# Narrow_AAA_sensor.net
KiCad netlist of a schematic drawn in EAGLE
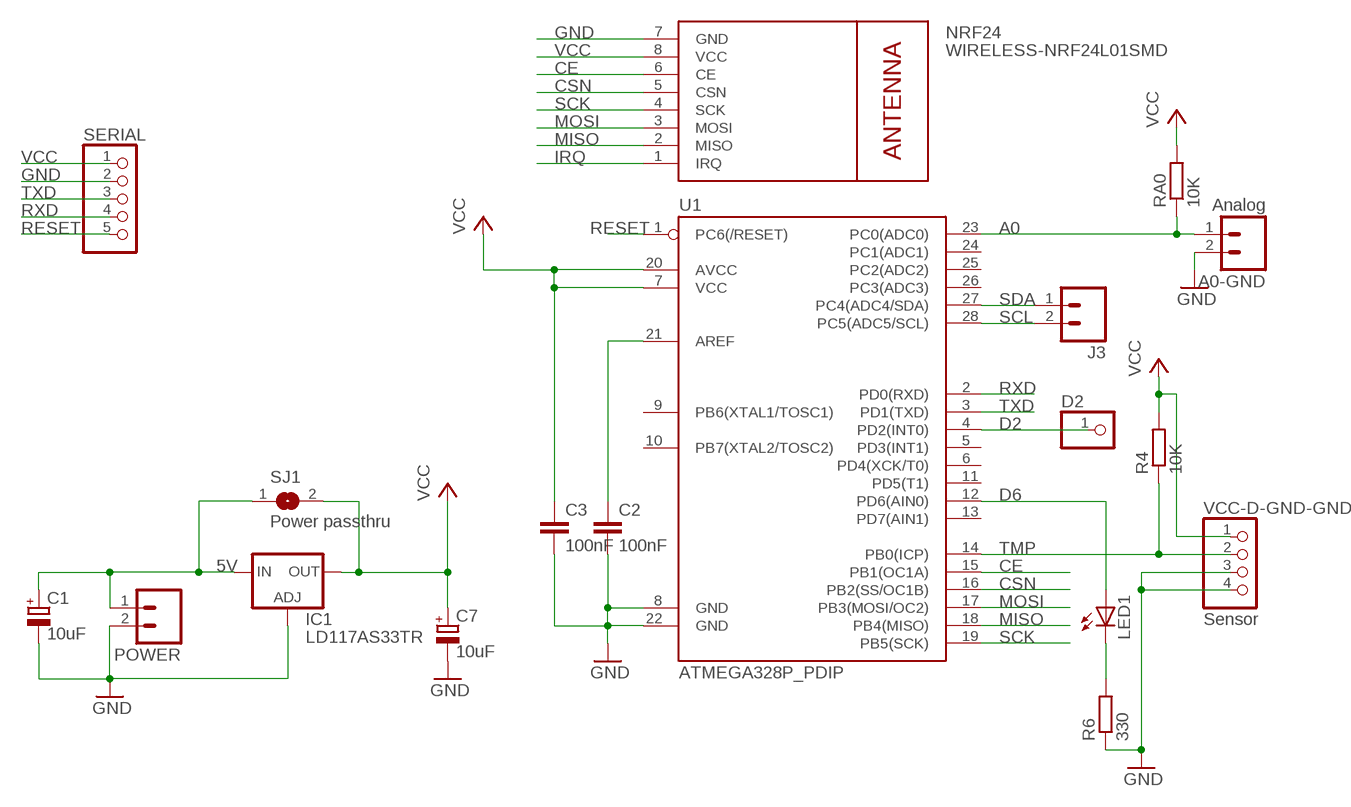
[diagram p0: schematic, sheet 1]

(export (version "E")
  (design (tool "Eeschema 10.0.6"))
  (components
    (comp (ref "A0-GND")
      (value "Analog")
      (footprint "eagle-import:1X02")
      (libsource (lib "eagle-import") (part "M02PTH"))
    )
    (comp (ref "C1")
      (value "10uF")
      (footprint "eagle-import:E2,5-5")
      (libsource (lib "eagle-import") (part "CPOL-EUE2.5-5"))
    )
    (comp (ref "C2")
      (value "100nF")
      (footprint "eagle-import:C025-025X050")
      (libsource (lib "eagle-import") (part "C-EU025-025X050"))
    )
    (comp (ref "C3")
      (value "100nF")
      (footprint "eagle-import:C025-025X050")
      (libsource (lib "eagle-import") (part "C-EU025-025X050"))
    )
    (comp (ref "C7")
      (value "10uF")
      (footprint "eagle-import:E2,5-5")
      (libsource (lib "eagle-import") (part "CPOL-EUE2.5-5"))
    )
    (comp (ref "D2")
      (value "PINHD-1X1")
      (footprint "eagle-import:1X01")
      (libsource (lib "eagle-import") (part "PINHD-1X1"))
    )
    (comp (ref "IC1")
      (value "LD117AS33TR")
      (footprint "eagle-import:SOT223")
      (libsource (lib "eagle-import") (part "LD117A?S33TR"))
    )
    (comp (ref "J3")
      (value "M021X02_NO_SILK")
      (footprint "eagle-import:1X02_NO_SILK")
      (libsource (lib "eagle-import") (part "M021X02_NO_SILK"))
    )
    (comp (ref "LED1")
      (value "LED3MM")
      (footprint "eagle-import:LED3MM")
      (libsource (lib "eagle-import") (part "LED3MM"))
    )
    (comp (ref "NRF24")
      (value "WIRELESS-NRF24L01SMD")
      (footprint "eagle-import:WIRELESS-NRF24L01-SMD")
      (libsource (lib "eagle-import") (part "WIRELESS-NRF24L01SMD"))
    )
    (comp (ref "POWER")
      (value "M021X02_NO_SILK")
      (footprint "eagle-import:1X02_NO_SILK")
      (libsource (lib "eagle-import") (part "M021X02_NO_SILK"))
    )
    (comp (ref "R4")
      (value "10K")
      (footprint "eagle-import:0204_7")
      (libsource (lib "eagle-import") (part "R-EU_0204/7"))
    )
    (comp (ref "R6")
      (value "330")
      (footprint "eagle-import:0204_7")
      (libsource (lib "eagle-import") (part "R-EU_0204/7"))
    )
    (comp (ref "RA0")
      (value "10K")
      (footprint "eagle-import:0204_7")
      (libsource (lib "eagle-import") (part "R-EU_0204/7"))
    )
    (comp (ref "SERIAL")
      (value "PINHD-1X5")
      (footprint "eagle-import:1X05")
      (libsource (lib "eagle-import") (part "PINHD-1X5"))
    )
    (comp (ref "SJ1")
      (value "Power passthru")
      (footprint "eagle-import:SJ")
      (libsource (lib "eagle-import") (part "SJ"))
    )
    (comp (ref "U1")
      (value "ATMEGA328P_PDIP")
      (footprint "eagle-import:DIL28-3")
      (libsource (lib "eagle-import") (part "ATMEGA328P_PDIP"))
    )
    (comp (ref "VCC-D-GND-GND")
      (value "Sensor")
      (footprint "eagle-import:1X04")
      (libsource (lib "eagle-import") (part "PINHD-1X4"))
    )
  )
  (nets
    (net (code "1") (name "/5V") (class "Default")
      (node (ref "C1") (pin "+") (pinfunction "+_+") (pintype "passive"))
      (node (ref "IC1") (pin "3") (pinfunction "IN_3") (pintype "input"))
      (node (ref "POWER") (pin "1") (pinfunction "1_1") (pintype "passive"))
      (node (ref "SJ1") (pin "1") (pinfunction "1_1") (pintype "passive"))
    )
    (net (code "2") (name "/A0") (class "Default")
      (node (ref "A0-GND") (pin "1") (pinfunction "1_1") (pintype "passive"))
      (node (ref "RA0") (pin "1") (pinfunction "1_1") (pintype "passive"))
      (node (ref "U1") (pin "23") (pinfunction "PC0(ADC0)_23") (pintype "bidirectional"))
    )
    (net (code "3") (name "/CE") (class "Default")
      (node (ref "NRF24") (pin "6") (pinfunction "CE_6") (pintype "bidirectional"))
      (node (ref "U1") (pin "15") (pinfunction "PB1(OC1A)_15") (pintype "bidirectional"))
    )
    (net (code "4") (name "/CSN") (class "Default")
      (node (ref "NRF24") (pin "5") (pinfunction "CSN_5") (pintype "bidirectional"))
      (node (ref "U1") (pin "16") (pinfunction "PB2(SS/OC1B)_16") (pintype "bidirectional"))
    )
    (net (code "5") (name "/D2") (class "Default")
      (node (ref "D2") (pin "1") (pinfunction "1_1") (pintype "passive"))
      (node (ref "U1") (pin "4") (pinfunction "PD2(INT0)_4") (pintype "bidirectional"))
    )
    (net (code "6") (name "/D6") (class "Default")
      (node (ref "LED1") (pin "A") (pinfunction "A_A") (pintype "passive"))
      (node (ref "U1") (pin "12") (pinfunction "PD6(AIN0)_12") (pintype "bidirectional"))
    )
    (net (code "7") (name "/IRQ") (class "Default")
      (node (ref "NRF24") (pin "1") (pinfunction "IRQ_1") (pintype "bidirectional"))
    )
    (net (code "8") (name "/MISO") (class "Default")
      (node (ref "NRF24") (pin "2") (pinfunction "MISO_2") (pintype "bidirectional"))
      (node (ref "U1") (pin "18") (pinfunction "PB4(MISO)_18") (pintype "bidirectional"))
    )
    (net (code "9") (name "/MOSI") (class "Default")
      (node (ref "NRF24") (pin "3") (pinfunction "MOSI_3") (pintype "bidirectional"))
      (node (ref "U1") (pin "17") (pinfunction "PB3(MOSI/OC2)_17") (pintype "bidirectional"))
    )
    (net (code "10") (name "/RESET") (class "Default")
      (node (ref "SERIAL") (pin "5") (pinfunction "5_5") (pintype "passive"))
      (node (ref "U1") (pin "1") (pinfunction "PC6(/RESET)_1") (pintype "bidirectional"))
    )
    (net (code "11") (name "/RXD") (class "Default")
      (node (ref "SERIAL") (pin "4") (pinfunction "4_4") (pintype "passive"))
      (node (ref "U1") (pin "2") (pinfunction "PD0(RXD)_2") (pintype "bidirectional"))
    )
    (net (code "12") (name "/SCK") (class "Default")
      (node (ref "NRF24") (pin "4") (pinfunction "SCK_4") (pintype "bidirectional"))
      (node (ref "U1") (pin "19") (pinfunction "PB5(SCK)_19") (pintype "bidirectional"))
    )
    (net (code "13") (name "/SCL") (class "Default")
      (node (ref "J3") (pin "2") (pinfunction "2_2") (pintype "passive"))
      (node (ref "U1") (pin "28") (pinfunction "PC5(ADC5/SCL)_28") (pintype "bidirectional"))
    )
    (net (code "14") (name "/SDA") (class "Default")
      (node (ref "J3") (pin "1") (pinfunction "1_1") (pintype "passive"))
      (node (ref "U1") (pin "27") (pinfunction "PC4(ADC4/SDA)_27") (pintype "bidirectional"))
    )
    (net (code "15") (name "/TMP") (class "Default")
      (node (ref "R4") (pin "1") (pinfunction "1_1") (pintype "passive"))
      (node (ref "U1") (pin "14") (pinfunction "PB0(ICP)_14") (pintype "bidirectional"))
      (node (ref "VCC-D-GND-GND") (pin "2") (pinfunction "2_2") (pintype "passive"))
    )
    (net (code "16") (name "/TXD") (class "Default")
      (node (ref "SERIAL") (pin "3") (pinfunction "3_3") (pintype "passive"))
      (node (ref "U1") (pin "3") (pinfunction "PD1(TXD)_3") (pintype "bidirectional"))
    )
    (net (code "17") (name "GND") (class "Default")
      (node (ref "A0-GND") (pin "2") (pinfunction "2_2") (pintype "passive"))
      (node (ref "C1") (pin "-") (pinfunction "-_-") (pintype "passive"))
      (node (ref "C2") (pin "2") (pinfunction "2_2") (pintype "passive"))
      (node (ref "C3") (pin "2") (pinfunction "2_2") (pintype "passive"))
      (node (ref "C7") (pin "-") (pinfunction "-_-") (pintype "passive"))
      (node (ref "IC1") (pin "1") (pinfunction "ADJ_1") (pintype "input"))
      (node (ref "NRF24") (pin "7") (pinfunction "GND_7") (pintype "power_in"))
      (node (ref "POWER") (pin "2") (pinfunction "2_2") (pintype "passive"))
      (node (ref "R6") (pin "1") (pinfunction "1_1") (pintype "passive"))
      (node (ref "SERIAL") (pin "2") (pinfunction "2_2") (pintype "passive"))
      (node (ref "U1") (pin "22") (pinfunction "GND_22") (pintype "bidirectional"))
      (node (ref "U1") (pin "8") (pinfunction "GND_8") (pintype "bidirectional"))
      (node (ref "VCC-D-GND-GND") (pin "3") (pinfunction "3_3") (pintype "passive"))
      (node (ref "VCC-D-GND-GND") (pin "4") (pinfunction "4_4") (pintype "passive"))
    )
    (net (code "18") (name "Net-(LED1-C)") (class "Default")
      (node (ref "LED1") (pin "K") (pinfunction "C_K") (pintype "passive"))
      (node (ref "R6") (pin "2") (pinfunction "2_2") (pintype "passive"))
    )
    (net (code "19") (name "Net-(U1-AREF)") (class "Default")
      (node (ref "C2") (pin "1") (pinfunction "1_1") (pintype "passive"))
      (node (ref "U1") (pin "21") (pinfunction "AREF_21") (pintype "bidirectional"))
    )
    (net (code "20") (name "VCC") (class "Default")
      (node (ref "C3") (pin "1") (pinfunction "1_1") (pintype "passive"))
      (node (ref "C7") (pin "+") (pinfunction "+_+") (pintype "passive"))
      (node (ref "IC1") (pin "4") (pinfunction "OUT_4") (pintype "passive"))
      (node (ref "NRF24") (pin "8") (pinfunction "VCC_8") (pintype "power_in"))
      (node (ref "R4") (pin "2") (pinfunction "2_2") (pintype "passive"))
      (node (ref "RA0") (pin "2") (pinfunction "2_2") (pintype "passive"))
      (node (ref "SERIAL") (pin "1") (pinfunction "1_1") (pintype "passive"))
      (node (ref "SJ1") (pin "2") (pinfunction "2_2") (pintype "passive"))
      (node (ref "U1") (pin "20") (pinfunction "AVCC_20") (pintype "bidirectional"))
      (node (ref "U1") (pin "7") (pinfunction "VCC_7") (pintype "bidirectional"))
      (node (ref "VCC-D-GND-GND") (pin "1") (pinfunction "1_1") (pintype "passive"))
    )
    (net (code "21") (name "unconnected-(U1-PB6(XTAL1{slash}TOSC1)-Pad9)") (class "Default")
      (node (ref "U1") (pin "9") (pinfunction "PB6(XTAL1/TOSC1)_9") (pintype "bidirectional"))
    )
    (net (code "22") (name "unconnected-(U1-PB7(XTAL2{slash}TOSC2)-Pad10)") (class "Default")
      (node (ref "U1") (pin "10") (pinfunction "PB7(XTAL2/TOSC2)_10") (pintype "bidirectional"))
    )
    (net (code "23") (name "unconnected-(U1-PC1(ADC1)-Pad24)") (class "Default")
      (node (ref "U1") (pin "24") (pinfunction "PC1(ADC1)_24") (pintype "bidirectional"))
    )
    (net (code "24") (name "unconnected-(U1-PC2(ADC2)-Pad25)") (class "Default")
      (node (ref "U1") (pin "25") (pinfunction "PC2(ADC2)_25") (pintype "bidirectional"))
    )
    (net (code "25") (name "unconnected-(U1-PC3(ADC3)-Pad26)") (class "Default")
      (node (ref "U1") (pin "26") (pinfunction "PC3(ADC3)_26") (pintype "bidirectional"))
    )
    (net (code "26") (name "unconnected-(U1-PD3(INT1)-Pad5)") (class "Default")
      (node (ref "U1") (pin "5") (pinfunction "PD3(INT1)_5") (pintype "bidirectional"))
    )
    (net (code "27") (name "unconnected-(U1-PD4(XCK{slash}T0)-Pad6)") (class "Default")
      (node (ref "U1") (pin "6") (pinfunction "PD4(XCK/T0)_6") (pintype "bidirectional"))
    )
    (net (code "28") (name "unconnected-(U1-PD5(T1)-Pad11)") (class "Default")
      (node (ref "U1") (pin "11") (pinfunction "PD5(T1)_11") (pintype "bidirectional"))
    )
    (net (code "29") (name "unconnected-(U1-PD7(AIN1)-Pad13)") (class "Default")
      (node (ref "U1") (pin "13") (pinfunction "PD7(AIN1)_13") (pintype "bidirectional"))
    )
  )
)
